# GSM.net
KiCad netlist of a schematic drawn in Altium Designer
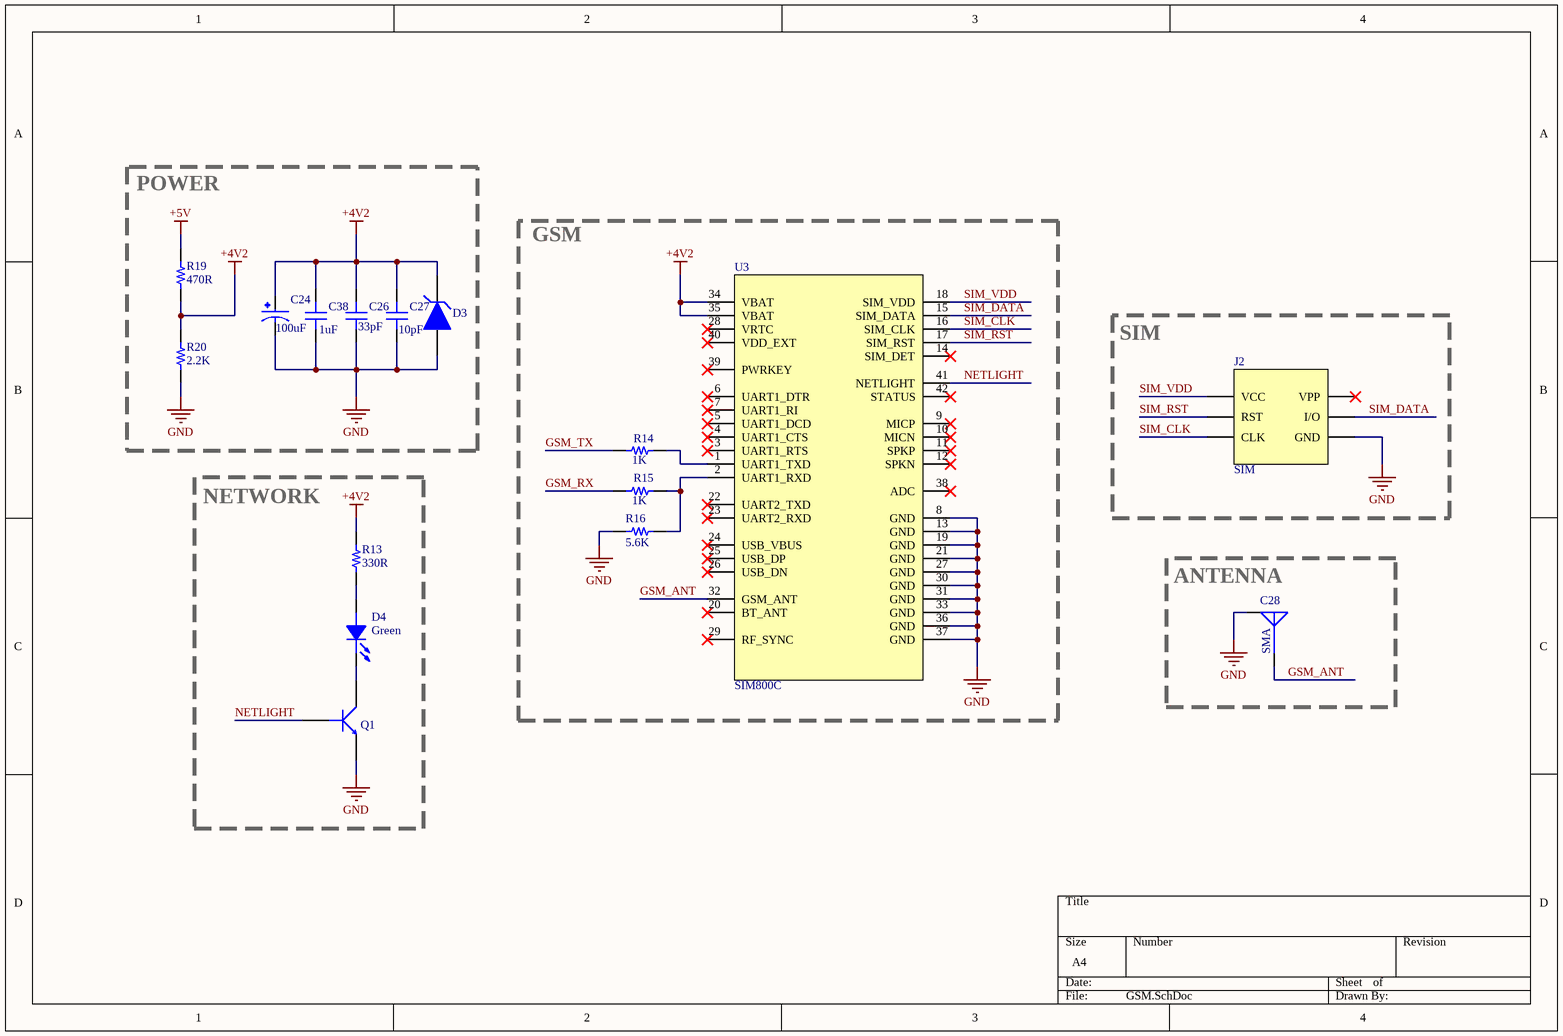
[diagram p0: GSM.SchDoc]

(export (version "E")
  (design (tool "Eeschema 10.0.6"))
  (components
    (comp (ref "C24")
      (value "100uF")
      (footprint "TANTAL B-CASE")
      (description "TANTAL")
      (libsource (lib "hava_kalitesi_olcumu") (part "100uF"))
    )
    (comp (ref "C26")
      (value "33pF")
      (footprint "CAP 0603_1608")
      (description "CERAMİC 1206 SMD")
      (libsource (lib "hava_kalitesi_olcumu") (part "33pF"))
    )
    (comp (ref "C27")
      (value "10pF")
      (footprint "CAP 0603_1608")
      (description "CERAMİC 1206 SMD")
      (libsource (lib "hava_kalitesi_olcumu") (part "10pF"))
    )
    (comp (ref "C28")
      (value "SMA")
      (footprint "132134-11 SMA ANTEN")
      (description "SMA Anten Connector")
      (libsource (lib "hava_kalitesi_olcumu") (part "Anten SMA  2"))
    )
    (comp (ref "C38")
      (value "1uF")
      (footprint "CAP 0603_1608")
      (description "CERAMİC 1206 SMD")
      (libsource (lib "hava_kalitesi_olcumu") (part "1uF"))
    )
    (comp (ref "D3")
      (value "ZENER DIODE")
      (footprint "SOD123")
      (description "SOD123")
      (fields
        (field (name "MANUFACTURER") "ON Semiconductor")
        (field (name "MANUFACTURER PART NUMBER") "1SMB5919BT3G")
      )
      (libsource (lib "hava_kalitesi_olcumu") (part "ZENER DIODE"))
    )
    (comp (ref "D4")
      (value "Green")
      (footprint "0805 Green LED")
      (fields
        (field (name "MANUFACTURER") "AVAGO Technologies")
        (field (name "VOLTAGE") "2.2V")
        (field (name "Comment") "0805 Green LED")
      )
      (libsource (lib "hava_kalitesi_olcumu") (part "0805 Green LED"))
    )
    (comp (ref "J2")
      (value "SIM")
      (footprint "GCT_SIM7100-6-1-15-00-A_REVC")
      (description "Memory Card Connectors Micro SIM Card Connector - Push-Push Type, 6 Pin, SMT, 1.50mm Profile")
      (fields (field (name "MP") "SIM7100-6-1-15-00-A") (field (name "MF") "Global Connector Technology"))
      (libsource (lib "hava_kalitesi_olcumu") (part "SIM7100-6-1-15-00-A"))
    )
    (comp (ref "Q1")
      (value "MMBT3904-7-F")
      (footprint "SOT-23F")
      (description "Transistor General Purpose BJT NPN 40 Volt 0.2A Automotive 3-Pin SOT-23")
      (fields (field (name "MANUFACTURER") "Diodes Zetex") (field (name "DESIGNED BY") "BERK"))
      (libsource (lib "hava_kalitesi_olcumu") (part "MMBT3904-7-F"))
    )
    (comp (ref "R13")
      (value "330R")
      (footprint "RES 0603_1608")
      (description "SMT RES 1206")
      (libsource (lib "hava_kalitesi_olcumu") (part "330R"))
    )
    (comp (ref "R14")
      (value "1K")
      (footprint "RES 0603_1608")
      (description "SMT RES 1206")
      (libsource (lib "hava_kalitesi_olcumu") (part "1K"))
    )
    (comp (ref "R15")
      (value "1K")
      (footprint "RES 0603_1608")
      (description "SMT RES 1206")
      (libsource (lib "hava_kalitesi_olcumu") (part "1K"))
    )
    (comp (ref "R16")
      (value "5.6K")
      (footprint "RES 0603_1608")
      (description "SMT RES 1206")
      (libsource (lib "hava_kalitesi_olcumu") (part "5.6K"))
    )
    (comp (ref "R19")
      (value "470R")
      (footprint "RES 0603_1608")
      (description "SMT RES 1206")
      (libsource (lib "hava_kalitesi_olcumu") (part "470R"))
    )
    (comp (ref "R20")
      (value "2.2K")
      (footprint "RES 0603_1608")
      (description "SMT RES 1206")
      (libsource (lib "hava_kalitesi_olcumu") (part "2.2K"))
    )
    (comp (ref "U3")
      (value "SIM800C")
      (footprint "LCC110P1570X1760X250-42N")
      (description "GSM/Bluetooth")
      (libsource (lib "hava_kalitesi_olcumu") (part "SIM800C"))
    )
  )
  (nets
    (net (code "1") (name "+4V2") (class "Default")
      (node (ref "C24") (pin "+") (pinfunction "+_+") (pintype "passive"))
      (node (ref "C26") (pin "2") (pinfunction "2_2") (pintype "passive"))
      (node (ref "C27") (pin "2") (pinfunction "2_2") (pintype "passive"))
      (node (ref "C38") (pin "2") (pinfunction "2_2") (pintype "passive"))
      (node (ref "D3") (pin "C") (pinfunction "C_C") (pintype "passive"))
      (node (ref "R13") (pin "2") (pinfunction "2_2") (pintype "passive"))
      (node (ref "R19") (pin "1") (pinfunction "1_1") (pintype "passive"))
      (node (ref "R20") (pin "2") (pinfunction "2_2") (pintype "passive"))
      (node (ref "U3") (pin "34") (pinfunction "VBAT_34") (pintype "power_in"))
      (node (ref "U3") (pin "35") (pinfunction "VBAT_35") (pintype "power_in"))
    )
    (net (code "2") (name "+5V") (class "Default")
      (node (ref "R19") (pin "2") (pinfunction "2_2") (pintype "passive"))
    )
    (net (code "3") (name "/GSM_ANT") (class "Default")
      (node (ref "C28") (pin "S") (pinfunction "S_S") (pintype "passive"))
      (node (ref "U3") (pin "32") (pinfunction "GSM_ANT_32") (pintype "power_in"))
    )
    (net (code "4") (name "/GSM_RX") (class "Default")
      (node (ref "R15") (pin "1") (pinfunction "1_1") (pintype "passive"))
    )
    (net (code "5") (name "/GSM_TX") (class "Default")
      (node (ref "R14") (pin "1") (pinfunction "1_1") (pintype "passive"))
    )
    (net (code "6") (name "/NETLIGHT") (class "Default")
      (node (ref "Q1") (pin "1") (pinfunction "B_1") (pintype "power_in"))
      (node (ref "U3") (pin "41") (pinfunction "NETLIGHT_41") (pintype "power_in"))
    )
    (net (code "7") (name "/SIM_CLK") (class "Default")
      (node (ref "J2") (pin "C3") (pinfunction "CLK_C3") (pintype "power_in"))
      (node (ref "U3") (pin "16") (pinfunction "SIM_CLK_16") (pintype "power_in"))
    )
    (net (code "8") (name "/SIM_DATA") (class "Default")
      (node (ref "J2") (pin "C7") (pinfunction "I/O_C7") (pintype "power_in"))
      (node (ref "U3") (pin "15") (pinfunction "SIM_DATA_15") (pintype "power_in"))
    )
    (net (code "9") (name "/SIM_RST") (class "Default")
      (node (ref "J2") (pin "C2") (pinfunction "RST_C2") (pintype "power_in"))
      (node (ref "U3") (pin "17") (pinfunction "SIM_RST_17") (pintype "power_in"))
    )
    (net (code "10") (name "/SIM_VDD") (class "Default")
      (node (ref "J2") (pin "C1") (pinfunction "VCC_C1") (pintype "power_in"))
      (node (ref "U3") (pin "18") (pinfunction "SIM_VDD_18") (pintype "power_in"))
    )
    (net (code "11") (name "GND") (class "Default")
      (node (ref "C24") (pin "-") (pinfunction "-_-") (pintype "passive"))
      (node (ref "C26") (pin "1") (pinfunction "1_1") (pintype "passive"))
      (node (ref "C27") (pin "1") (pinfunction "1_1") (pintype "passive"))
      (node (ref "C28") (pin "G") (pinfunction "G_G") (pintype "passive"))
      (node (ref "C38") (pin "1") (pinfunction "1_1") (pintype "passive"))
      (node (ref "D3") (pin "A") (pinfunction "A_A") (pintype "passive"))
      (node (ref "J2") (pin "C5") (pinfunction "GND_C5") (pintype "power_in"))
      (node (ref "Q1") (pin "2") (pinfunction "E_2") (pintype "power_in"))
      (node (ref "R16") (pin "1") (pinfunction "1_1") (pintype "passive"))
      (node (ref "R20") (pin "1") (pinfunction "1_1") (pintype "passive"))
      (node (ref "U3") (pin "13") (pinfunction "GND_13") (pintype "power_in"))
      (node (ref "U3") (pin "19") (pinfunction "GND_19") (pintype "power_in"))
      (node (ref "U3") (pin "21") (pinfunction "GND_21") (pintype "power_in"))
      (node (ref "U3") (pin "27") (pinfunction "GND_27") (pintype "power_in"))
      (node (ref "U3") (pin "30") (pinfunction "GND_30") (pintype "power_in"))
      (node (ref "U3") (pin "31") (pinfunction "GND_31") (pintype "power_in"))
      (node (ref "U3") (pin "33") (pinfunction "GND_33") (pintype "power_in"))
      (node (ref "U3") (pin "36") (pinfunction "GND_36") (pintype "power_in"))
      (node (ref "U3") (pin "37") (pinfunction "GND_37") (pintype "power_in"))
      (node (ref "U3") (pin "8") (pinfunction "GND_8") (pintype "power_in"))
    )
    (net (code "12") (name "Net-(D4-ANODE)") (class "Default")
      (node (ref "D4") (pin "1") (pinfunction "ANODE_1") (pintype "passive"))
      (node (ref "R13") (pin "1") (pinfunction "1_1") (pintype "passive"))
    )
    (net (code "13") (name "Net-(D4-CATHODE)") (class "Default")
      (node (ref "D4") (pin "2") (pinfunction "CATHODE_2") (pintype "passive"))
      (node (ref "Q1") (pin "3") (pinfunction "C_3") (pintype "power_in"))
    )
    (net (code "14") (name "Net-(U3-UART1_RXD)") (class "Default")
      (node (ref "R15") (pin "2") (pinfunction "2_2") (pintype "passive"))
      (node (ref "R16") (pin "2") (pinfunction "2_2") (pintype "passive"))
      (node (ref "U3") (pin "2") (pinfunction "UART1_RXD_2") (pintype "power_in"))
    )
    (net (code "15") (name "Net-(U3-UART1_TXD)") (class "Default")
      (node (ref "R14") (pin "2") (pinfunction "2_2") (pintype "passive"))
      (node (ref "U3") (pin "1") (pinfunction "UART1_TXD_1") (pintype "power_in"))
    )
    (net (code "16") (name "unconnected-(J2-VPP-PadC6)") (class "Default")
      (node (ref "J2") (pin "C6") (pinfunction "VPP_C6") (pintype "power_in+no_connect"))
    )
    (net (code "17") (name "unconnected-(U3-ADC-Pad38)") (class "Default")
      (node (ref "U3") (pin "38") (pinfunction "ADC_38") (pintype "power_in+no_connect"))
    )
    (net (code "18") (name "unconnected-(U3-BT_ANT-Pad20)") (class "Default")
      (node (ref "U3") (pin "20") (pinfunction "BT_ANT_20") (pintype "power_in+no_connect"))
    )
    (net (code "19") (name "unconnected-(U3-MICN-Pad10)") (class "Default")
      (node (ref "U3") (pin "10") (pinfunction "MICN_10") (pintype "power_in+no_connect"))
    )
    (net (code "20") (name "unconnected-(U3-MICP-Pad9)") (class "Default")
      (node (ref "U3") (pin "9") (pinfunction "MICP_9") (pintype "power_in+no_connect"))
    )
    (net (code "21") (name "unconnected-(U3-PWRKEY-Pad39)") (class "Default")
      (node (ref "U3") (pin "39") (pinfunction "PWRKEY_39") (pintype "power_in+no_connect"))
    )
    (net (code "22") (name "unconnected-(U3-RF_SYNC-Pad29)") (class "Default")
      (node (ref "U3") (pin "29") (pinfunction "RF_SYNC_29") (pintype "power_in+no_connect"))
    )
    (net (code "23") (name "unconnected-(U3-SIM_DET-Pad14)") (class "Default")
      (node (ref "U3") (pin "14") (pinfunction "SIM_DET_14") (pintype "power_in+no_connect"))
    )
    (net (code "24") (name "unconnected-(U3-SPKN-Pad12)") (class "Default")
      (node (ref "U3") (pin "12") (pinfunction "SPKN_12") (pintype "power_in+no_connect"))
    )
    (net (code "25") (name "unconnected-(U3-SPKP-Pad11)") (class "Default")
      (node (ref "U3") (pin "11") (pinfunction "SPKP_11") (pintype "power_in+no_connect"))
    )
    (net (code "26") (name "unconnected-(U3-STATUS-Pad42)") (class "Default")
      (node (ref "U3") (pin "42") (pinfunction "STATUS_42") (pintype "power_in+no_connect"))
    )
    (net (code "27") (name "unconnected-(U3-UART1_CTS-Pad4)") (class "Default")
      (node (ref "U3") (pin "4") (pinfunction "UART1_CTS_4") (pintype "power_in+no_connect"))
    )
    (net (code "28") (name "unconnected-(U3-UART1_DCD-Pad5)") (class "Default")
      (node (ref "U3") (pin "5") (pinfunction "UART1_DCD_5") (pintype "power_in+no_connect"))
    )
    (net (code "29") (name "unconnected-(U3-UART1_DTR-Pad6)") (class "Default")
      (node (ref "U3") (pin "6") (pinfunction "UART1_DTR_6") (pintype "power_in+no_connect"))
    )
    (net (code "30") (name "unconnected-(U3-UART1_RI-Pad7)") (class "Default")
      (node (ref "U3") (pin "7") (pinfunction "UART1_RI_7") (pintype "power_in+no_connect"))
    )
    (net (code "31") (name "unconnected-(U3-UART1_RTS-Pad3)") (class "Default")
      (node (ref "U3") (pin "3") (pinfunction "UART1_RTS_3") (pintype "power_in+no_connect"))
    )
    (net (code "32") (name "unconnected-(U3-UART2_RXD-Pad23)") (class "Default")
      (node (ref "U3") (pin "23") (pinfunction "UART2_RXD_23") (pintype "power_in+no_connect"))
    )
    (net (code "33") (name "unconnected-(U3-UART2_TXD-Pad22)") (class "Default")
      (node (ref "U3") (pin "22") (pinfunction "UART2_TXD_22") (pintype "power_in+no_connect"))
    )
    (net (code "34") (name "unconnected-(U3-USB_DN-Pad26)") (class "Default")
      (node (ref "U3") (pin "26") (pinfunction "USB_DN_26") (pintype "power_in+no_connect"))
    )
    (net (code "35") (name "unconnected-(U3-USB_DP-Pad25)") (class "Default")
      (node (ref "U3") (pin "25") (pinfunction "USB_DP_25") (pintype "power_in+no_connect"))
    )
    (net (code "36") (name "unconnected-(U3-USB_VBUS-Pad24)") (class "Default")
      (node (ref "U3") (pin "24") (pinfunction "USB_VBUS_24") (pintype "power_in+no_connect"))
    )
    (net (code "37") (name "unconnected-(U3-VDD_EXT-Pad40)") (class "Default")
      (node (ref "U3") (pin "40") (pinfunction "VDD_EXT_40") (pintype "power_in+no_connect"))
    )
    (net (code "38") (name "unconnected-(U3-VRTC-Pad28)") (class "Default")
      (node (ref "U3") (pin "28") (pinfunction "VRTC_28") (pintype "power_in+no_connect"))
    )
  )
)
